# TundraHaptics.net
KiCad netlist of a schematic drawn in Altium Designer
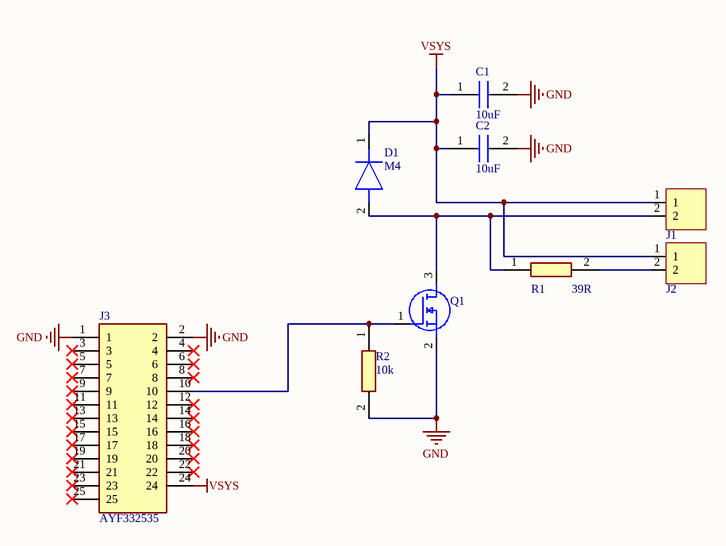
[diagram p0: TundraHaptics.SchDoc]

(export (version "E")
  (design (tool "Eeschema 10.0.6"))
  (components
    (comp (ref "C1")
      (value "10uF")
      (footprint "TundraHaptics:CAPC2012X140N")
      (description "Capacitor")
      (fields (field (name "MANUFACTURER_PART_NUMBER") "C0805C106K8PACTU-2.5"))
      (libsource (lib "TundraHaptics") (part "C0805C106K8PACTU-2.5"))
    )
    (comp (ref "C2")
      (value "10uF")
      (footprint "TundraHaptics:CAPC2012X140N")
      (description "Capacitor")
      (fields (field (name "MANUFACTURER_PART_NUMBER") "C0805C106K8PACTU-2.5"))
      (libsource (lib "TundraHaptics") (part "C0805C106K8PACTU-2.5"))
    )
    (comp (ref "D1")
      (value "M4")
      (footprint "TundraHaptics:DIOM5327X240N")
      (description "Diode")
      (fields (field (name "MOUSER PART NUMBER") "637-M4"))
      (libsource (lib "TundraHaptics") (part "M4"))
    )
    (comp (ref "J1")
      (value "Haptic Pads")
      (footprint "Haptic Pads")
      (libsource (lib "TundraHaptics") (part "Haptic Pads"))
    )
    (comp (ref "J2")
      (value "Haptic Pads")
      (footprint "Haptic Pads")
      (libsource (lib "TundraHaptics") (part "Haptic Pads"))
    )
    (comp (ref "J3")
      (value "AYF332535")
      (footprint "TundraHaptics:AYF332535")
      (description "Connector")
      (fields (field (name "MOUSER PART NUMBER") "769-AYF332535"))
      (libsource (lib "TundraHaptics") (part "AYF332535"))
    )
    (comp (ref "Q1")
      (value "N Channel Mosfet")
      (footprint "SOT95P237X112-3N")
      (description "Mosfet")
      (libsource (lib "TundraHaptics") (part "SI2302CDS-T1-E3"))
    )
    (comp (ref "R1")
      (value "39R")
      (footprint "TundraHaptics:RESC3116X65N")
      (description "39R Resistor")
      (fields
        (field (name "MANUFACTURER_PART_NUMBER") "RC1206FR-0739RL")
        (field (name "MOUSER PART NUMBER") "603-RC1206FR-0739RL")
      )
      (libsource (lib "TundraHaptics") (part "RC1206FR-0751RL"))
    )
    (comp (ref "R2")
      (value "10k")
      (footprint "TundraHaptics:RESC1608X55N")
      (description "Resistor")
      (fields
        (field (name "MANUFACTURER_PART_NUMBER") "RC0603FR-0710KL")
        (field (name "MOUSER PART NUMBER") "603-RC0603FR-0710KL")
      )
      (libsource (lib "TundraHaptics") (part "RC0603FR-0710KL"))
    )
  )
  (nets
    (net (code "1") (name "GND") (class "Default")
      (node (ref "C1") (pin "2") (pinfunction "2_2") (pintype "passive"))
      (node (ref "C2") (pin "2") (pinfunction "2_2") (pintype "passive"))
      (node (ref "J3") (pin "1") (pinfunction "1_1") (pintype "passive"))
      (node (ref "J3") (pin "2") (pinfunction "2_2") (pintype "passive"))
      (node (ref "Q1") (pin "2") (pinfunction "S_2") (pintype "passive"))
      (node (ref "R2") (pin "2") (pinfunction "2_2") (pintype "passive"))
    )
    (net (code "2") (name "Net-(D1-A)") (class "Default")
      (node (ref "D1") (pin "2") (pinfunction "A_2") (pintype "passive"))
      (node (ref "J1") (pin "2") (pinfunction "2_2") (pintype "passive"))
      (node (ref "Q1") (pin "3") (pinfunction "D_3") (pintype "passive"))
      (node (ref "R1") (pin "1") (pinfunction "1_1") (pintype "passive"))
    )
    (net (code "3") (name "Net-(J2-Pad2)") (class "Default")
      (node (ref "J2") (pin "2") (pinfunction "2_2") (pintype "passive"))
      (node (ref "R1") (pin "2") (pinfunction "2_2") (pintype "passive"))
    )
    (net (code "4") (name "Net-(Q1-G)") (class "Default")
      (node (ref "J3") (pin "10") (pinfunction "10_10") (pintype "passive"))
      (node (ref "Q1") (pin "1") (pinfunction "G_1") (pintype "passive"))
      (node (ref "R2") (pin "1") (pinfunction "1_1") (pintype "passive"))
    )
    (net (code "5") (name "VSYS") (class "Default")
      (node (ref "C1") (pin "1") (pinfunction "1_1") (pintype "passive"))
      (node (ref "C2") (pin "1") (pinfunction "1_1") (pintype "passive"))
      (node (ref "D1") (pin "1") (pinfunction "K_1") (pintype "passive"))
      (node (ref "J1") (pin "1") (pinfunction "1_1") (pintype "passive"))
      (node (ref "J2") (pin "1") (pinfunction "1_1") (pintype "passive"))
      (node (ref "J3") (pin "24") (pinfunction "24_24") (pintype "passive"))
    )
    (net (code "6") (name "unconnected-(J3-Pad3)") (class "Default")
      (node (ref "J3") (pin "3") (pinfunction "3_3") (pintype "passive+no_connect"))
    )
    (net (code "7") (name "unconnected-(J3-Pad4)") (class "Default")
      (node (ref "J3") (pin "4") (pinfunction "4_4") (pintype "passive+no_connect"))
    )
    (net (code "8") (name "unconnected-(J3-Pad5)") (class "Default")
      (node (ref "J3") (pin "5") (pinfunction "5_5") (pintype "passive+no_connect"))
    )
    (net (code "9") (name "unconnected-(J3-Pad6)") (class "Default")
      (node (ref "J3") (pin "6") (pinfunction "6_6") (pintype "passive+no_connect"))
    )
    (net (code "10") (name "unconnected-(J3-Pad7)") (class "Default")
      (node (ref "J3") (pin "7") (pinfunction "7_7") (pintype "passive+no_connect"))
    )
    (net (code "11") (name "unconnected-(J3-Pad8)") (class "Default")
      (node (ref "J3") (pin "8") (pinfunction "8_8") (pintype "passive+no_connect"))
    )
    (net (code "12") (name "unconnected-(J3-Pad9)") (class "Default")
      (node (ref "J3") (pin "9") (pinfunction "9_9") (pintype "passive+no_connect"))
    )
    (net (code "13") (name "unconnected-(J3-Pad11)") (class "Default")
      (node (ref "J3") (pin "11") (pinfunction "11_11") (pintype "passive+no_connect"))
    )
    (net (code "14") (name "unconnected-(J3-Pad12)") (class "Default")
      (node (ref "J3") (pin "12") (pinfunction "12_12") (pintype "passive+no_connect"))
    )
    (net (code "15") (name "unconnected-(J3-Pad13)") (class "Default")
      (node (ref "J3") (pin "13") (pinfunction "13_13") (pintype "passive+no_connect"))
    )
    (net (code "16") (name "unconnected-(J3-Pad14)") (class "Default")
      (node (ref "J3") (pin "14") (pinfunction "14_14") (pintype "passive+no_connect"))
    )
    (net (code "17") (name "unconnected-(J3-Pad15)") (class "Default")
      (node (ref "J3") (pin "15") (pinfunction "15_15") (pintype "passive+no_connect"))
    )
    (net (code "18") (name "unconnected-(J3-Pad16)") (class "Default")
      (node (ref "J3") (pin "16") (pinfunction "16_16") (pintype "passive+no_connect"))
    )
    (net (code "19") (name "unconnected-(J3-Pad17)") (class "Default")
      (node (ref "J3") (pin "17") (pinfunction "17_17") (pintype "passive+no_connect"))
    )
    (net (code "20") (name "unconnected-(J3-Pad18)") (class "Default")
      (node (ref "J3") (pin "18") (pinfunction "18_18") (pintype "passive+no_connect"))
    )
    (net (code "21") (name "unconnected-(J3-Pad19)") (class "Default")
      (node (ref "J3") (pin "19") (pinfunction "19_19") (pintype "passive+no_connect"))
    )
    (net (code "22") (name "unconnected-(J3-Pad20)") (class "Default")
      (node (ref "J3") (pin "20") (pinfunction "20_20") (pintype "passive+no_connect"))
    )
    (net (code "23") (name "unconnected-(J3-Pad21)") (class "Default")
      (node (ref "J3") (pin "21") (pinfunction "21_21") (pintype "passive+no_connect"))
    )
    (net (code "24") (name "unconnected-(J3-Pad22)") (class "Default")
      (node (ref "J3") (pin "22") (pinfunction "22_22") (pintype "passive+no_connect"))
    )
    (net (code "25") (name "unconnected-(J3-Pad23)") (class "Default")
      (node (ref "J3") (pin "23") (pinfunction "23_23") (pintype "passive+no_connect"))
    )
    (net (code "26") (name "unconnected-(J3-Pad25)") (class "Default")
      (node (ref "J3") (pin "25") (pinfunction "25_25") (pintype "passive+no_connect"))
    )
  )
)
